# Sheet1.net
KiCad netlist of a schematic drawn in Altium Designer
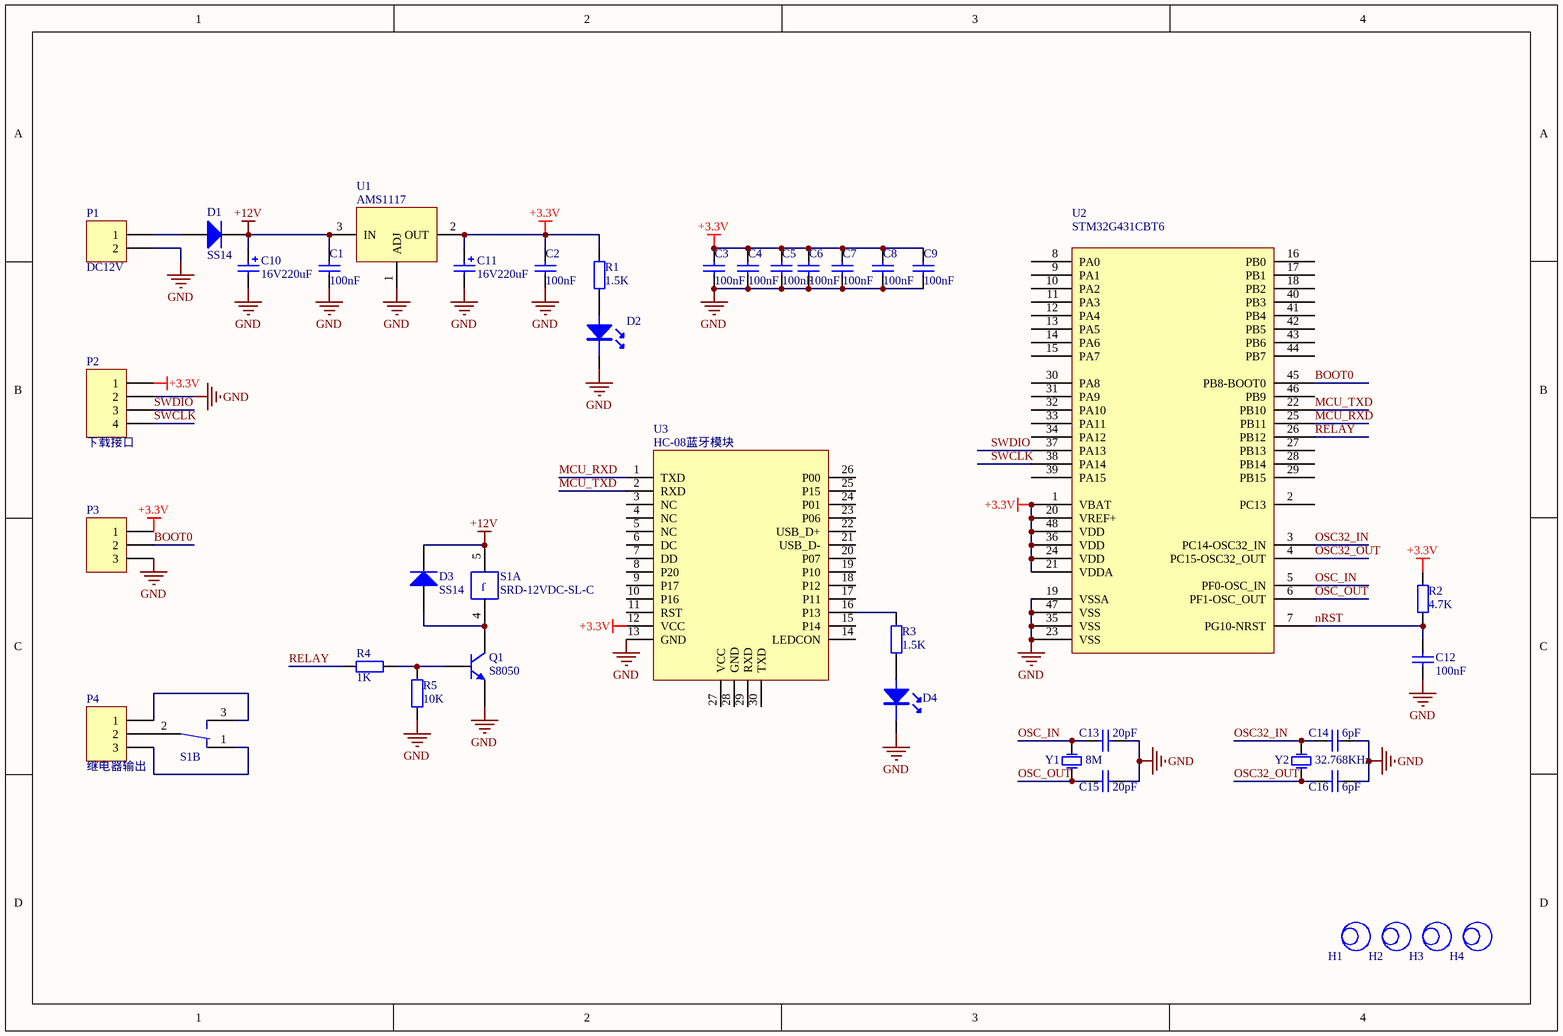
[diagram p0: Sheet1.SchDoc]

(export (version "E")
  (design (tool "Eeschema 10.0.6"))
  (components
    (comp (ref "C1")
      (value "100nF")
      (footprint "0603M")
      (description "贴片电容")
      (libsource (lib "FourAxis") (part "Cap"))
    )
    (comp (ref "C2")
      (value "100nF")
      (footprint "0603M")
      (description "贴片电容")
      (libsource (lib "FourAxis") (part "Cap"))
    )
    (comp (ref "C3")
      (value "100nF")
      (footprint "0603M")
      (description "贴片电容")
      (libsource (lib "FourAxis") (part "Cap"))
    )
    (comp (ref "C4")
      (value "100nF")
      (footprint "0603M")
      (description "贴片电容")
      (libsource (lib "FourAxis") (part "Cap"))
    )
    (comp (ref "C5")
      (value "100nF")
      (footprint "0603M")
      (description "贴片电容")
      (libsource (lib "FourAxis") (part "Cap"))
    )
    (comp (ref "C6")
      (value "100nF")
      (footprint "0603M")
      (description "贴片电容")
      (libsource (lib "FourAxis") (part "Cap"))
    )
    (comp (ref "C7")
      (value "100nF")
      (footprint "0603M")
      (description "贴片电容")
      (libsource (lib "FourAxis") (part "Cap"))
    )
    (comp (ref "C8")
      (value "100nF")
      (footprint "0603M")
      (description "贴片电容")
      (libsource (lib "FourAxis") (part "Cap"))
    )
    (comp (ref "C9")
      (value "100nF")
      (footprint "0603M")
      (description "贴片电容")
      (libsource (lib "FourAxis") (part "Cap"))
    )
    (comp (ref "C10")
      (value "16V220uF")
      (footprint "CAP-6.3x7.7")
      (description "电解电容")
      (fields (field (name "PUBLISHER") "Altium Limited"))
      (libsource (lib "Schematic Library") (part "ECAP"))
    )
    (comp (ref "C11")
      (value "16V220uF")
      (footprint "CAP-6.3x7.7")
      (description "电解电容")
      (fields (field (name "PUBLISHER") "Altium Limited"))
      (libsource (lib "Schematic Library") (part "ECAP"))
    )
    (comp (ref "C12")
      (value "100nF")
      (footprint "0603M")
      (description "贴片电容")
      (libsource (lib "FourAxis") (part "Cap"))
    )
    (comp (ref "C13")
      (value "20pF")
      (footprint "0603M")
      (description "贴片电容")
      (libsource (lib "FourAxis") (part "Cap"))
    )
    (comp (ref "C14")
      (value "6pF")
      (footprint "0603M")
      (description "贴片电容")
      (libsource (lib "FourAxis") (part "Cap"))
    )
    (comp (ref "C15")
      (value "20pF")
      (footprint "0603M")
      (description "贴片电容")
      (libsource (lib "FourAxis") (part "Cap"))
    )
    (comp (ref "C16")
      (value "6pF")
      (footprint "0603M")
      (description "贴片电容")
      (libsource (lib "FourAxis") (part "Cap"))
    )
    (comp (ref "D1")
      (value "SS14")
      (footprint "SMA")
      (description "二极管")
      (fields (field (name "PUBLISHER") "Altium Limited"))
      (libsource (lib "Schematic Library") (part "Diode"))
    )
    (comp (ref "D2")
      (value "POWER")
      (footprint "LED-0805-R")
      (description "发光二极管")
      (libsource (lib "OLED-0.96-Demo-MCU+Board") (part "LED1"))
    )
    (comp (ref "D3")
      (value "SS14")
      (footprint "SMA")
      (description "二极管")
      (fields (field (name "PUBLISHER") "Altium Limited"))
      (libsource (lib "Schematic Library") (part "Diode"))
    )
    (comp (ref "D4")
      (value "POWER")
      (footprint "LED-0805-G")
      (description "发光二极管")
      (libsource (lib "OLED-0.96-Demo-MCU+Board") (part "LED1"))
    )
    (comp (ref "H1")
      (value "非金属化固定孔")
      (footprint "HOLE-3MM")
      (libsource (lib "Schematic Library") (part "Hole-非金属化固定孔"))
    )
    (comp (ref "H2")
      (value "非金属化固定孔")
      (footprint "HOLE-3MM")
      (libsource (lib "Schematic Library") (part "Hole-非金属化固定孔"))
    )
    (comp (ref "H3")
      (value "非金属化固定孔")
      (footprint "HOLE-3MM")
      (libsource (lib "Schematic Library") (part "Hole-非金属化固定孔"))
    )
    (comp (ref "H4")
      (value "非金属化固定孔")
      (footprint "HOLE-3MM")
      (libsource (lib "Schematic Library") (part "Hole-非金属化固定孔"))
    )
    (comp (ref "P1")
      (value "DC12V")
      (footprint "CON-KF2EDGK-5.08-W-2P")
      (description "Header, 2-Pin")
      (fields (field (name "PUBLISHER") "Altium Limited"))
      (libsource (lib "Schematic Library") (part "MHDR1X2"))
    )
    (comp (ref "P2")
      (value "下载接口")
      (footprint "HDR1X4")
      (description "Header, 4-Pin")
      (fields (field (name "PUBLISHER") "Altium Limited"))
      (libsource (lib "Miscellaneous Connectors") (part "Header 4"))
    )
    (comp (ref "P3")
      (value "MHDR1X3")
      (footprint "HDR1X3")
      (description "Header, 3-Pin")
      (fields (field (name "PUBLISHER") "Altium Limited"))
      (libsource (lib "Schematic Library") (part "MHDR1X3"))
    )
    (comp (ref "P4")
      (value "继电器输出")
      (footprint "CON-KF2EDGK-5.08-W-3P")
      (description "Header, 3-Pin")
      (fields (field (name "PUBLISHER") "Altium Limited"))
      (libsource (lib "Schematic Library") (part "MHDR1X3"))
    )
    (comp (ref "Q1")
      (value "S8050")
      (footprint "SOT-23")
      (description "Transistor-NPN")
      (libsource (lib "Schematic Library") (part "Transistor-NPN"))
    )
    (comp (ref "R1")
      (value "1.5K")
      (footprint "0603M")
      (description "贴片电阻")
      (libsource (lib "FourAxis") (part "电阻"))
    )
    (comp (ref "R2")
      (value "4.7K")
      (footprint "0603M")
      (description "贴片电阻")
      (libsource (lib "FourAxis") (part "电阻"))
    )
    (comp (ref "R3")
      (value "1.5K")
      (footprint "0603M")
      (description "贴片电阻")
      (libsource (lib "") (part "电阻_2"))
    )
    (comp (ref "R4") (value "1K") (footprint "0603M") (description "贴片电阻") (libsource (lib "") (part "电阻_1")))
    (comp (ref "R5")
      (value "10K")
      (footprint "0603M")
      (description "贴片电阻")
      (libsource (lib "") (part "电阻_2"))
    )
    (comp (ref "S1")
      (value "SRD-12VDC-SL-C")
      (footprint "SRD-05VDC-SL-C")
      (description "Relay")
      (libsource (lib "Schematic Library") (part "RELAY-SRD-05VDC-SL-C-SP"))
    )
    (comp (ref "U1")
      (value "AMS1117")
      (footprint "SOT-223-M")
      (description "线性稳压芯片")
      (libsource (lib "Schematic Library") (part "AMS1117"))
    )
    (comp (ref "U2")
      (value "STM32G431CBT6")
      (footprint "LQFP48")
      (libsource (lib "Schematic Library") (part "STM32G431CBT6"))
    )
    (comp (ref "U3")
      (value "HC-08蓝牙模块")
      (footprint "HC-02/04/08/08B/42")
      (libsource (lib "Schematic Library") (part "HC-08"))
    )
    (comp (ref "Y1")
      (value "8M")
      (footprint "X-49/S_N")
      (description "晶振（直插）")
      (fields (field (name "PUBLISHER") "Altium Limited"))
      (libsource (lib "OLED-0.96-Demo-MCU+Board") (part "XTAL_1"))
    )
    (comp (ref "Y2")
      (value "32.768KHz")
      (footprint "X-2X6")
      (description "晶振（直插）")
      (fields (field (name "PUBLISHER") "Altium Limited"))
      (libsource (lib "OLED-0.96-Demo-MCU+Board") (part "XTAL_1"))
    )
  )
  (nets
    (net (code "1") (name "+3.3V") (class "Default")
      (node (ref "C11") (pin "1") (pinfunction "1_1") (pintype "passive"))
      (node (ref "C2") (pin "2") (pinfunction "2_2") (pintype "passive"))
      (node (ref "C3") (pin "2") (pinfunction "2_2") (pintype "passive"))
      (node (ref "C4") (pin "2") (pinfunction "2_2") (pintype "passive"))
      (node (ref "C5") (pin "2") (pinfunction "2_2") (pintype "passive"))
      (node (ref "C6") (pin "2") (pinfunction "2_2") (pintype "passive"))
      (node (ref "C7") (pin "2") (pinfunction "2_2") (pintype "passive"))
      (node (ref "C8") (pin "2") (pinfunction "2_2") (pintype "passive"))
      (node (ref "C9") (pin "2") (pinfunction "2_2") (pintype "passive"))
      (node (ref "P2") (pin "1") (pinfunction "1_1") (pintype "passive"))
      (node (ref "P3") (pin "1") (pinfunction "1_1") (pintype "passive"))
      (node (ref "R1") (pin "2") (pinfunction "2_2") (pintype "passive"))
      (node (ref "R2") (pin "2") (pinfunction "2_2") (pintype "passive"))
      (node (ref "U1") (pin "2") (pinfunction "OUT_2") (pintype "passive"))
      (node (ref "U2") (pin "1") (pinfunction "VBAT_1") (pintype "passive"))
      (node (ref "U2") (pin "20") (pinfunction "VREF+_20") (pintype "passive"))
      (node (ref "U2") (pin "21") (pinfunction "VDDA_21") (pintype "passive"))
      (node (ref "U2") (pin "24") (pinfunction "VDD_24") (pintype "passive"))
      (node (ref "U2") (pin "36") (pinfunction "VDD_36") (pintype "passive"))
      (node (ref "U2") (pin "48") (pinfunction "VDD_48") (pintype "passive"))
      (node (ref "U3") (pin "12") (pinfunction "VCC_12") (pintype "passive"))
    )
    (net (code "2") (name "+12V") (class "Default")
      (node (ref "C1") (pin "2") (pinfunction "2_2") (pintype "passive"))
      (node (ref "C10") (pin "1") (pinfunction "1_1") (pintype "passive"))
      (node (ref "D1") (pin "2") (pinfunction "K_2") (pintype "passive"))
      (node (ref "D3") (pin "2") (pinfunction "K_2") (pintype "passive"))
      (node (ref "S1") (pin "5") (pinfunction "K2_5") (pintype "passive"))
      (node (ref "U1") (pin "3") (pinfunction "IN_3") (pintype "passive"))
    )
    (net (code "3") (name "/BOOT0") (class "Default")
      (node (ref "P3") (pin "2") (pinfunction "2_2") (pintype "passive"))
      (node (ref "U2") (pin "45") (pinfunction "PB8-BOOT0_45") (pintype "passive"))
    )
    (net (code "4") (name "/MCU_RXD") (class "Default")
      (node (ref "U2") (pin "25") (pinfunction "PB11_25") (pintype "passive"))
      (node (ref "U3") (pin "1") (pinfunction "TXD_1") (pintype "passive"))
    )
    (net (code "5") (name "/MCU_TXD") (class "Default")
      (node (ref "U2") (pin "22") (pinfunction "PB10_22") (pintype "passive"))
      (node (ref "U3") (pin "2") (pinfunction "RXD_2") (pintype "passive"))
    )
    (net (code "6") (name "/OSC32_IN") (class "Default")
      (node (ref "C14") (pin "1") (pinfunction "1_1") (pintype "passive"))
      (node (ref "U2") (pin "3") (pinfunction "PC14-OSC32_IN_3") (pintype "passive"))
      (node (ref "Y2") (pin "1") (pinfunction "1_1") (pintype "passive"))
    )
    (net (code "7") (name "/OSC32_OUT") (class "Default")
      (node (ref "C16") (pin "1") (pinfunction "1_1") (pintype "passive"))
      (node (ref "U2") (pin "4") (pinfunction "PC15-OSC32_OUT_4") (pintype "passive"))
      (node (ref "Y2") (pin "2") (pinfunction "2_2") (pintype "passive"))
    )
    (net (code "8") (name "/OSC_IN") (class "Default")
      (node (ref "C13") (pin "1") (pinfunction "1_1") (pintype "passive"))
      (node (ref "U2") (pin "5") (pinfunction "PF0-OSC_IN_5") (pintype "passive"))
      (node (ref "Y1") (pin "1") (pinfunction "1_1") (pintype "passive"))
    )
    (net (code "9") (name "/OSC_OUT") (class "Default")
      (node (ref "C15") (pin "1") (pinfunction "1_1") (pintype "passive"))
      (node (ref "U2") (pin "6") (pinfunction "PF1-OSC_OUT_6") (pintype "passive"))
      (node (ref "Y1") (pin "2") (pinfunction "2_2") (pintype "passive"))
    )
    (net (code "10") (name "/RELAY") (class "Default")
      (node (ref "R4") (pin "1") (pinfunction "1_1") (pintype "passive"))
      (node (ref "U2") (pin "26") (pinfunction "PB12_26") (pintype "passive"))
    )
    (net (code "11") (name "/SWCLK") (class "Default")
      (node (ref "P2") (pin "4") (pinfunction "4_4") (pintype "passive"))
      (node (ref "U2") (pin "38") (pinfunction "PA14_38") (pintype "passive"))
    )
    (net (code "12") (name "/SWDIO") (class "Default")
      (node (ref "P2") (pin "3") (pinfunction "3_3") (pintype "passive"))
      (node (ref "U2") (pin "37") (pinfunction "PA13_37") (pintype "passive"))
    )
    (net (code "13") (name "/nRST") (class "Default")
      (node (ref "C12") (pin "2") (pinfunction "2_2") (pintype "passive"))
      (node (ref "R2") (pin "1") (pinfunction "1_1") (pintype "passive"))
      (node (ref "U2") (pin "7") (pinfunction "PG10-NRST_7") (pintype "passive"))
    )
    (net (code "14") (name "GND") (class "Default")
      (node (ref "C1") (pin "1") (pinfunction "1_1") (pintype "passive"))
      (node (ref "C10") (pin "2") (pinfunction "2_2") (pintype "passive"))
      (node (ref "C11") (pin "2") (pinfunction "2_2") (pintype "passive"))
      (node (ref "C12") (pin "1") (pinfunction "1_1") (pintype "passive"))
      (node (ref "C13") (pin "2") (pinfunction "2_2") (pintype "passive"))
      (node (ref "C14") (pin "2") (pinfunction "2_2") (pintype "passive"))
      (node (ref "C15") (pin "2") (pinfunction "2_2") (pintype "passive"))
      (node (ref "C16") (pin "2") (pinfunction "2_2") (pintype "passive"))
      (node (ref "C2") (pin "1") (pinfunction "1_1") (pintype "passive"))
      (node (ref "C3") (pin "1") (pinfunction "1_1") (pintype "passive"))
      (node (ref "C4") (pin "1") (pinfunction "1_1") (pintype "passive"))
      (node (ref "C5") (pin "1") (pinfunction "1_1") (pintype "passive"))
      (node (ref "C6") (pin "1") (pinfunction "1_1") (pintype "passive"))
      (node (ref "C7") (pin "1") (pinfunction "1_1") (pintype "passive"))
      (node (ref "C8") (pin "1") (pinfunction "1_1") (pintype "passive"))
      (node (ref "C9") (pin "1") (pinfunction "1_1") (pintype "passive"))
      (node (ref "D2") (pin "2") (pinfunction "K_2") (pintype "passive"))
      (node (ref "D4") (pin "2") (pinfunction "K_2") (pintype "passive"))
      (node (ref "P1") (pin "2") (pinfunction "2_2") (pintype "passive"))
      (node (ref "P2") (pin "2") (pinfunction "2_2") (pintype "passive"))
      (node (ref "P3") (pin "3") (pinfunction "3_3") (pintype "passive"))
      (node (ref "Q1") (pin "2") (pinfunction "E_2") (pintype "passive"))
      (node (ref "R5") (pin "2") (pinfunction "2_2") (pintype "passive"))
      (node (ref "U1") (pin "1") (pinfunction "ADJ_1") (pintype "passive"))
      (node (ref "U2") (pin "19") (pinfunction "VSSA_19") (pintype "passive"))
      (node (ref "U2") (pin "23") (pinfunction "VSS_23") (pintype "passive"))
      (node (ref "U2") (pin "35") (pinfunction "VSS_35") (pintype "passive"))
      (node (ref "U2") (pin "47") (pinfunction "VSS_47") (pintype "passive"))
      (node (ref "U3") (pin "13") (pinfunction "GND_13") (pintype "passive"))
    )
    (net (code "15") (name "Net-(D1-A)") (class "Default")
      (node (ref "D1") (pin "1") (pinfunction "A_1") (pintype "passive"))
      (node (ref "P1") (pin "1") (pinfunction "1_1") (pintype "passive"))
    )
    (net (code "16") (name "Net-(D2-A)") (class "Default")
      (node (ref "D2") (pin "1") (pinfunction "A_1") (pintype "passive"))
      (node (ref "R1") (pin "1") (pinfunction "1_1") (pintype "passive"))
    )
    (net (code "17") (name "Net-(D3-A)") (class "Default")
      (node (ref "D3") (pin "1") (pinfunction "A_1") (pintype "passive"))
      (node (ref "Q1") (pin "3") (pinfunction "C_3") (pintype "passive"))
      (node (ref "S1") (pin "4") (pinfunction "K1_4") (pintype "passive"))
    )
    (net (code "18") (name "Net-(D4-A)") (class "Default")
      (node (ref "D4") (pin "1") (pinfunction "A_1") (pintype "passive"))
      (node (ref "R3") (pin "2") (pinfunction "2_2") (pintype "passive"))
    )
    (net (code "19") (name "Net-(P4-Pad1)") (class "Default")
      (node (ref "P4") (pin "1") (pinfunction "1_1") (pintype "passive"))
      (node (ref "S1") (pin "3") (pintype "passive"))
    )
    (net (code "20") (name "Net-(P4-Pad2)") (class "Default")
      (node (ref "P4") (pin "2") (pinfunction "2_2") (pintype "passive"))
      (node (ref "S1") (pin "2") (pintype "passive"))
    )
    (net (code "21") (name "Net-(P4-Pad3)") (class "Default")
      (node (ref "P4") (pin "3") (pinfunction "3_3") (pintype "passive"))
      (node (ref "S1") (pin "1") (pintype "passive"))
    )
    (net (code "22") (name "Net-(Q1-B)") (class "Default")
      (node (ref "Q1") (pin "1") (pinfunction "B_1") (pintype "passive"))
      (node (ref "R4") (pin "2") (pinfunction "2_2") (pintype "passive"))
      (node (ref "R5") (pin "1") (pinfunction "1_1") (pintype "passive"))
    )
    (net (code "23") (name "Net-(U3-P13)") (class "Default")
      (node (ref "R3") (pin "1") (pinfunction "1_1") (pintype "passive"))
      (node (ref "U3") (pin "16") (pinfunction "P13_16") (pintype "passive"))
    )
    (net (code "24") (name "unconnected-(U2-PA0-Pad8)") (class "Default")
      (node (ref "U2") (pin "8") (pinfunction "PA0_8") (pintype "passive"))
    )
    (net (code "25") (name "unconnected-(U2-PA1-Pad9)") (class "Default")
      (node (ref "U2") (pin "9") (pinfunction "PA1_9") (pintype "passive"))
    )
    (net (code "26") (name "unconnected-(U2-PA2-Pad10)") (class "Default")
      (node (ref "U2") (pin "10") (pinfunction "PA2_10") (pintype "passive"))
    )
    (net (code "27") (name "unconnected-(U2-PA3-Pad11)") (class "Default")
      (node (ref "U2") (pin "11") (pinfunction "PA3_11") (pintype "passive"))
    )
    (net (code "28") (name "unconnected-(U2-PA4-Pad12)") (class "Default")
      (node (ref "U2") (pin "12") (pinfunction "PA4_12") (pintype "passive"))
    )
    (net (code "29") (name "unconnected-(U2-PA5-Pad13)") (class "Default")
      (node (ref "U2") (pin "13") (pinfunction "PA5_13") (pintype "passive"))
    )
    (net (code "30") (name "unconnected-(U2-PA6-Pad14)") (class "Default")
      (node (ref "U2") (pin "14") (pinfunction "PA6_14") (pintype "passive"))
    )
    (net (code "31") (name "unconnected-(U2-PA7-Pad15)") (class "Default")
      (node (ref "U2") (pin "15") (pinfunction "PA7_15") (pintype "passive"))
    )
    (net (code "32") (name "unconnected-(U2-PA8-Pad30)") (class "Default")
      (node (ref "U2") (pin "30") (pinfunction "PA8_30") (pintype "passive"))
    )
    (net (code "33") (name "unconnected-(U2-PA9-Pad31)") (class "Default")
      (node (ref "U2") (pin "31") (pinfunction "PA9_31") (pintype "passive"))
    )
    (net (code "34") (name "unconnected-(U2-PA10-Pad32)") (class "Default")
      (node (ref "U2") (pin "32") (pinfunction "PA10_32") (pintype "passive"))
    )
    (net (code "35") (name "unconnected-(U2-PA11-Pad33)") (class "Default")
      (node (ref "U2") (pin "33") (pinfunction "PA11_33") (pintype "passive"))
    )
    (net (code "36") (name "unconnected-(U2-PA12-Pad34)") (class "Default")
      (node (ref "U2") (pin "34") (pinfunction "PA12_34") (pintype "passive"))
    )
    (net (code "37") (name "unconnected-(U2-PA15-Pad39)") (class "Default")
      (node (ref "U2") (pin "39") (pinfunction "PA15_39") (pintype "passive"))
    )
    (net (code "38") (name "unconnected-(U2-PB0-Pad16)") (class "Default")
      (node (ref "U2") (pin "16") (pinfunction "PB0_16") (pintype "passive"))
    )
    (net (code "39") (name "unconnected-(U2-PB1-Pad17)") (class "Default")
      (node (ref "U2") (pin "17") (pinfunction "PB1_17") (pintype "passive"))
    )
    (net (code "40") (name "unconnected-(U2-PB2-Pad18)") (class "Default")
      (node (ref "U2") (pin "18") (pinfunction "PB2_18") (pintype "passive"))
    )
    (net (code "41") (name "unconnected-(U2-PB3-Pad40)") (class "Default")
      (node (ref "U2") (pin "40") (pinfunction "PB3_40") (pintype "passive"))
    )
    (net (code "42") (name "unconnected-(U2-PB4-Pad41)") (class "Default")
      (node (ref "U2") (pin "41") (pinfunction "PB4_41") (pintype "passive"))
    )
    (net (code "43") (name "unconnected-(U2-PB5-Pad42)") (class "Default")
      (node (ref "U2") (pin "42") (pinfunction "PB5_42") (pintype "passive"))
    )
    (net (code "44") (name "unconnected-(U2-PB6-Pad43)") (class "Default")
      (node (ref "U2") (pin "43") (pinfunction "PB6_43") (pintype "passive"))
    )
    (net (code "45") (name "unconnected-(U2-PB7-Pad44)") (class "Default")
      (node (ref "U2") (pin "44") (pinfunction "PB7_44") (pintype "passive"))
    )
    (net (code "46") (name "unconnected-(U2-PB9-Pad46)") (class "Default")
      (node (ref "U2") (pin "46") (pinfunction "PB9_46") (pintype "passive"))
    )
    (net (code "47") (name "unconnected-(U2-PB13-Pad27)") (class "Default")
      (node (ref "U2") (pin "27") (pinfunction "PB13_27") (pintype "passive"))
    )
    (net (code "48") (name "unconnected-(U2-PB14-Pad28)") (class "Default")
      (node (ref "U2") (pin "28") (pinfunction "PB14_28") (pintype "passive"))
    )
    (net (code "49") (name "unconnected-(U2-PB15-Pad29)") (class "Default")
      (node (ref "U2") (pin "29") (pinfunction "PB15_29") (pintype "passive"))
    )
    (net (code "50") (name "unconnected-(U2-PC13-Pad2)") (class "Default")
      (node (ref "U2") (pin "2") (pinfunction "PC13_2") (pintype "passive"))
    )
    (net (code "51") (name "unconnected-(U3-DC-Pad6)") (class "Default")
      (node (ref "U3") (pin "6") (pinfunction "DC_6") (pintype "passive"))
    )
    (net (code "52") (name "unconnected-(U3-DD-Pad7)") (class "Default")
      (node (ref "U3") (pin "7") (pinfunction "DD_7") (pintype "passive"))
    )
    (net (code "53") (name "unconnected-(U3-GND-Pad28)") (class "Default")
      (node (ref "U3") (pin "28") (pinfunction "GND_28") (pintype "passive"))
    )
    (net (code "54") (name "unconnected-(U3-LEDCON-Pad14)") (class "Default")
      (node (ref "U3") (pin "14") (pinfunction "LEDCON_14") (pintype "passive"))
    )
    (net (code "55") (name "unconnected-(U3-NC-Pad3)") (class "Default")
      (node (ref "U3") (pin "3") (pinfunction "NC_3") (pintype "passive"))
    )
    (net (code "56") (name "unconnected-(U3-NC-Pad4)") (class "Default")
      (node (ref "U3") (pin "4") (pinfunction "NC_4") (pintype "passive"))
    )
    (net (code "57") (name "unconnected-(U3-NC-Pad5)") (class "Default")
      (node (ref "U3") (pin "5") (pinfunction "NC_5") (pintype "passive"))
    )
    (net (code "58") (name "unconnected-(U3-P00-Pad26)") (class "Default")
      (node (ref "U3") (pin "26") (pinfunction "P00_26") (pintype "passive"))
    )
    (net (code "59") (name "unconnected-(U3-P01-Pad24)") (class "Default")
      (node (ref "U3") (pin "24") (pinfunction "P01_24") (pintype "passive"))
    )
    (net (code "60") (name "unconnected-(U3-P06-Pad23)") (class "Default")
      (node (ref "U3") (pin "23") (pinfunction "P06_23") (pintype "passive"))
    )
    (net (code "61") (name "unconnected-(U3-P07-Pad20)") (class "Default")
      (node (ref "U3") (pin "20") (pinfunction "P07_20") (pintype "passive"))
    )
    (net (code "62") (name "unconnected-(U3-P10-Pad19)") (class "Default")
      (node (ref "U3") (pin "19") (pinfunction "P10_19") (pintype "passive"))
    )
    (net (code "63") (name "unconnected-(U3-P11-Pad17)") (class "Default")
      (node (ref "U3") (pin "17") (pinfunction "P11_17") (pintype "passive"))
    )
    (net (code "64") (name "unconnected-(U3-P12-Pad18)") (class "Default")
      (node (ref "U3") (pin "18") (pinfunction "P12_18") (pintype "passive"))
    )
    (net (code "65") (name "unconnected-(U3-P14-Pad15)") (class "Default")
      (node (ref "U3") (pin "15") (pinfunction "P14_15") (pintype "passive"))
    )
    (net (code "66") (name "unconnected-(U3-P15-Pad25)") (class "Default")
      (node (ref "U3") (pin "25") (pinfunction "P15_25") (pintype "passive"))
    )
    (net (code "67") (name "unconnected-(U3-P16-Pad10)") (class "Default")
      (node (ref "U3") (pin "10") (pinfunction "P16_10") (pintype "passive"))
    )
    (net (code "68") (name "unconnected-(U3-P17-Pad9)") (class "Default")
      (node (ref "U3") (pin "9") (pinfunction "P17_9") (pintype "passive"))
    )
    (net (code "69") (name "unconnected-(U3-P20-Pad8)") (class "Default")
      (node (ref "U3") (pin "8") (pinfunction "P20_8") (pintype "passive"))
    )
    (net (code "70") (name "unconnected-(U3-RST-Pad11)") (class "Default")
      (node (ref "U3") (pin "11") (pinfunction "RST_11") (pintype "passive"))
    )
    (net (code "71") (name "unconnected-(U3-RXD-Pad29)") (class "Default")
      (node (ref "U3") (pin "29") (pinfunction "RXD_29") (pintype "passive"))
    )
    (net (code "72") (name "unconnected-(U3-TXD-Pad30)") (class "Default")
      (node (ref "U3") (pin "30") (pinfunction "TXD_30") (pintype "passive"))
    )
    (net (code "73") (name "unconnected-(U3-USB_D+-Pad22)") (class "Default")
      (node (ref "U3") (pin "22") (pinfunction "USB_D+_22") (pintype "passive"))
    )
    (net (code "74") (name "unconnected-(U3-USB_D--Pad21)") (class "Default")
      (node (ref "U3") (pin "21") (pinfunction "USB_D-_21") (pintype "passive"))
    )
    (net (code "75") (name "unconnected-(U3-VCC-Pad27)") (class "Default")
      (node (ref "U3") (pin "27") (pinfunction "VCC_27") (pintype "passive"))
    )
  )
)
